# sd2iec_sd_long.net
KiCad netlist of a schematic drawn in EAGLE
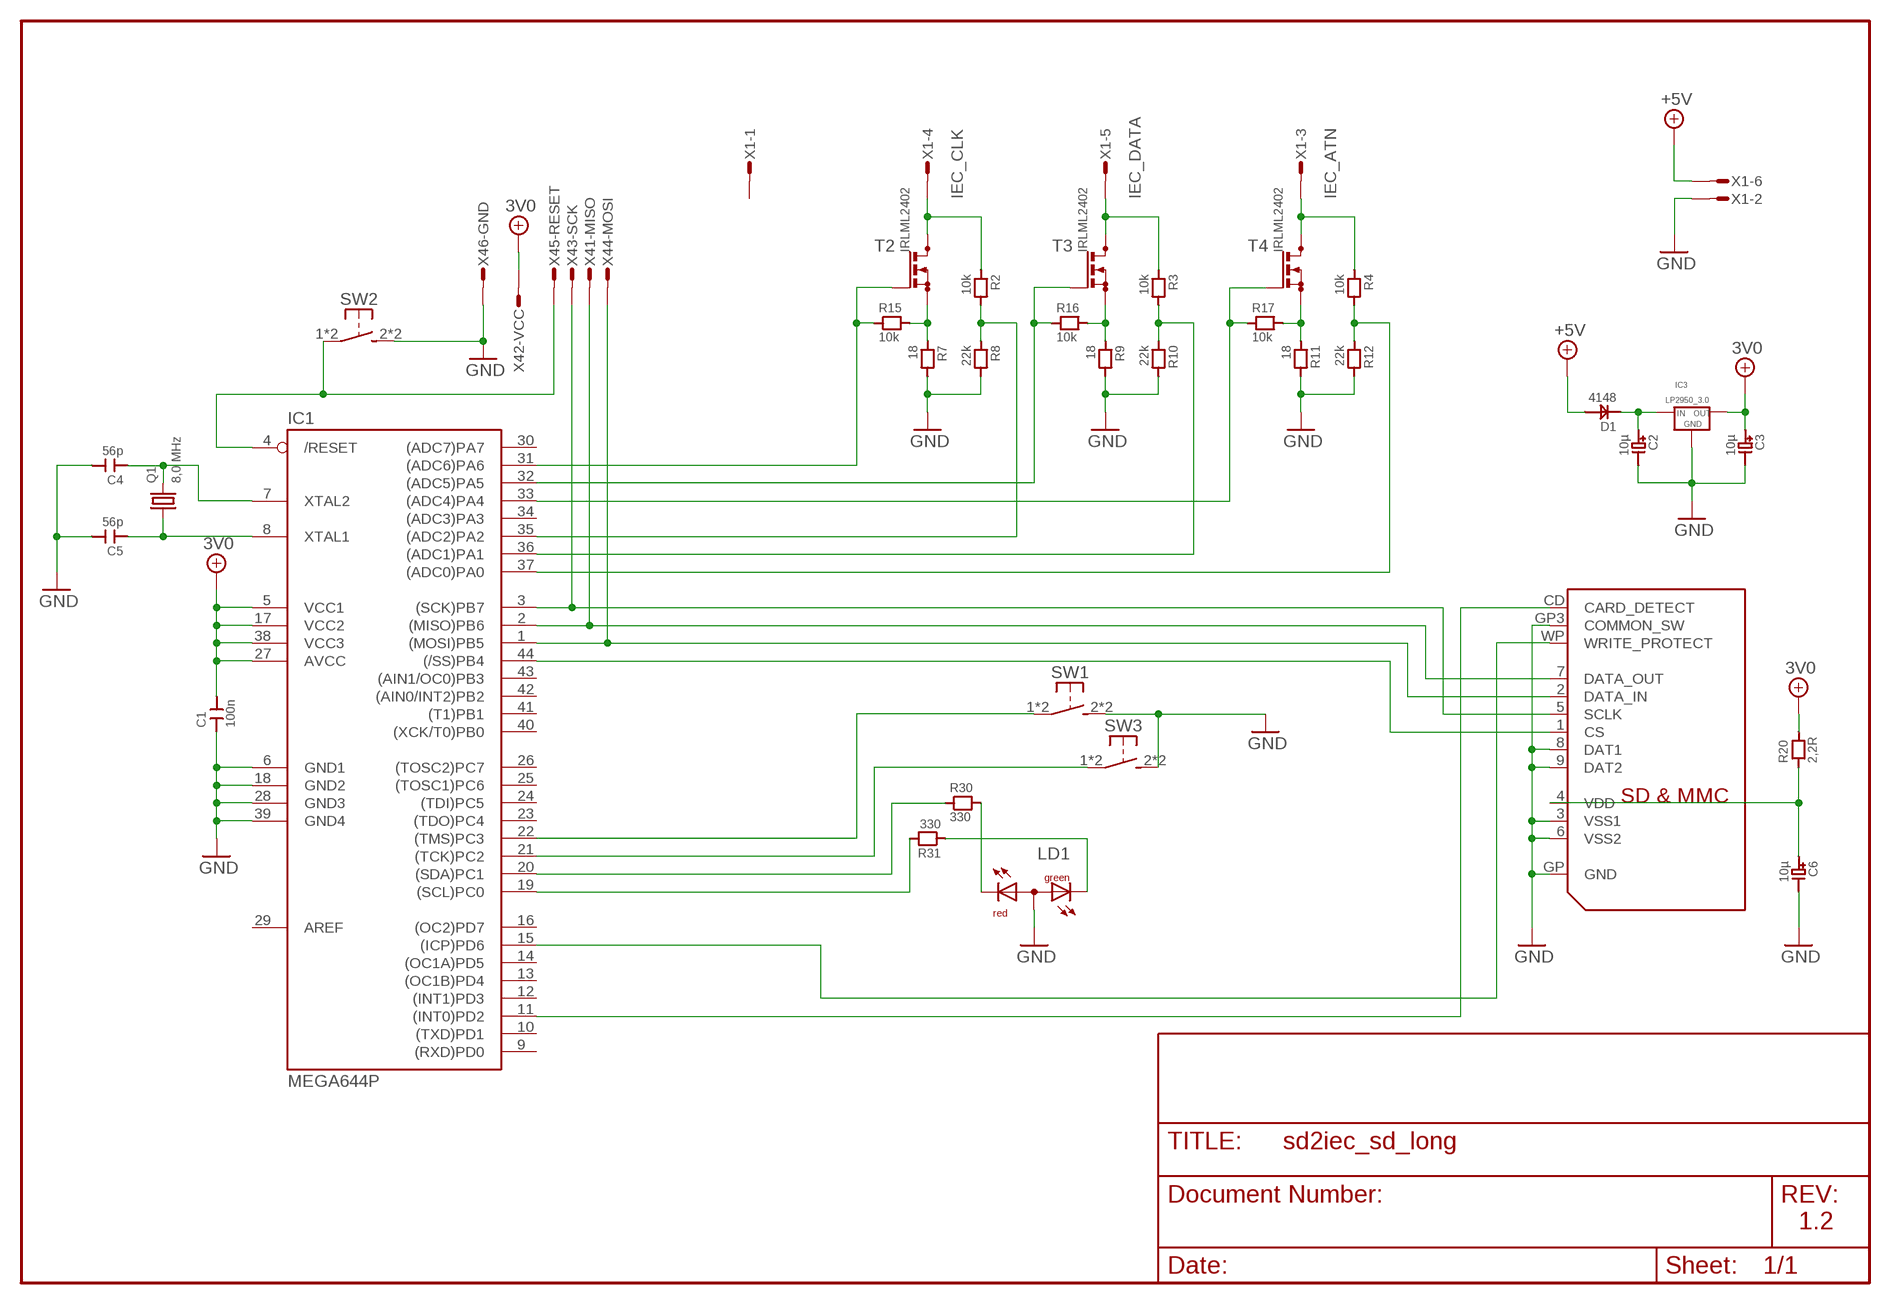
[diagram p0: schematic, sheet 1]

(export (version "E")
  (design (tool "Eeschema 10.0.6"))
  (components
    (comp (ref "C1")
      (value "100n")
      (footprint "eagle-import:C1206")
      (libsource (lib "eagle-import") (part "C1206"))
    )
    (comp (ref "C2")
      (value "10µ")
      (footprint "eagle-import:C_TANTAL_A")
      (libsource (lib "eagle-import") (part "C_POLTA_A"))
    )
    (comp (ref "C3")
      (value "10µ")
      (footprint "eagle-import:C_TANTAL_A")
      (libsource (lib "eagle-import") (part "C_POLTA_A"))
    )
    (comp (ref "C4")
      (value "56p")
      (footprint "eagle-import:C1206")
      (libsource (lib "eagle-import") (part "C1206"))
    )
    (comp (ref "C5")
      (value "56p")
      (footprint "eagle-import:C1206")
      (libsource (lib "eagle-import") (part "C1206"))
    )
    (comp (ref "C6")
      (value "10µ")
      (footprint "eagle-import:C_TANTAL_A")
      (libsource (lib "eagle-import") (part "C_POLTA_A"))
    )
    (comp (ref "D1")
      (value "4148")
      (footprint "eagle-import:SOD-123")
      (libsource (lib "eagle-import") (part "DSOD-123"))
    )
    (comp (ref "IC1")
      (value "MEGA644P")
      (footprint "eagle-import:TQFP44")
      (libsource (lib "eagle-import") (part "MEGA16/32TQFP"))
    )
    (comp (ref "IC3")
      (value "LP2950_3.0")
      (footprint "eagle-import:TO92_S")
      (libsource (lib "eagle-import") (part "LP2950_TO92S"))
    )
    (comp (ref "LD1")
      (value "DUOLED-RG-A")
      (footprint "eagle-import:DUOLED-A-5MM")
      (libsource (lib "eagle-import") (part "DUOLED-RG-A"))
    )
    (comp (ref "Q1")
      (value "8,0 MHz")
      (footprint "eagle-import:HC49_S")
      (libsource (lib "eagle-import") (part "HC49"))
    )
    (comp (ref "R2")
      (value "10k")
      (footprint "eagle-import:R1206")
      (libsource (lib "eagle-import") (part "R1206"))
    )
    (comp (ref "R3")
      (value "10k")
      (footprint "eagle-import:R1206")
      (libsource (lib "eagle-import") (part "R1206"))
    )
    (comp (ref "R4")
      (value "10k")
      (footprint "eagle-import:R1206")
      (libsource (lib "eagle-import") (part "R1206"))
    )
    (comp (ref "R7")
      (value "18")
      (footprint "eagle-import:R1206")
      (libsource (lib "eagle-import") (part "R1206"))
    )
    (comp (ref "R8")
      (value "22k")
      (footprint "eagle-import:R1206")
      (libsource (lib "eagle-import") (part "R1206"))
    )
    (comp (ref "R9")
      (value "18")
      (footprint "eagle-import:R1206")
      (libsource (lib "eagle-import") (part "R1206"))
    )
    (comp (ref "R10")
      (value "22k")
      (footprint "eagle-import:R1206")
      (libsource (lib "eagle-import") (part "R1206"))
    )
    (comp (ref "R11")
      (value "18")
      (footprint "eagle-import:R1206")
      (libsource (lib "eagle-import") (part "R1206"))
    )
    (comp (ref "R12")
      (value "22k")
      (footprint "eagle-import:R1206")
      (libsource (lib "eagle-import") (part "R1206"))
    )
    (comp (ref "R15")
      (value "10k")
      (footprint "eagle-import:R0805")
      (libsource (lib "eagle-import") (part "R0805"))
    )
    (comp (ref "R16")
      (value "10k")
      (footprint "eagle-import:R0805")
      (libsource (lib "eagle-import") (part "R0805"))
    )
    (comp (ref "R17")
      (value "10k")
      (footprint "eagle-import:R0805")
      (libsource (lib "eagle-import") (part "R0805"))
    )
    (comp (ref "R20")
      (value "2,2R")
      (footprint "eagle-import:R1206")
      (libsource (lib "eagle-import") (part "R1206"))
    )
    (comp (ref "R30")
      (value "330")
      (footprint "eagle-import:R1206")
      (libsource (lib "eagle-import") (part "R1206"))
    )
    (comp (ref "R31")
      (value "330")
      (footprint "eagle-import:R1206")
      (libsource (lib "eagle-import") (part "R1206"))
    )
    (comp (ref "SW1")
      (value "Disk Next")
      (footprint "eagle-import:TL3305")
      (libsource (lib "eagle-import") (part "SW-TACTILE-TL3305"))
    )
    (comp (ref "SW2")
      (value "Reset")
      (footprint "eagle-import:TL3305")
      (libsource (lib "eagle-import") (part "SW-TACTILE-TL3305"))
    )
    (comp (ref "SW3")
      (value "Disk Prev")
      (footprint "eagle-import:TL3305")
      (libsource (lib "eagle-import") (part "SW-TACTILE-TL3305"))
    )
    (comp (ref "T2")
      (value "IRLML2402")
      (footprint "eagle-import:SOT23_C")
      (libsource (lib "eagle-import") (part "BSN20_C"))
    )
    (comp (ref "T3")
      (value "IRLML2402")
      (footprint "eagle-import:SOT23_C")
      (libsource (lib "eagle-import") (part "BSN20_C"))
    )
    (comp (ref "T4")
      (value "IRLML2402")
      (footprint "eagle-import:SOT23_C")
      (libsource (lib "eagle-import") (part "BSN20_C"))
    )
    (comp (ref "U$6")
      (value "SDMMC06132")
      (footprint "eagle-import:06132")
      (libsource (lib "eagle-import") (part "SDMMC06132"))
    )
    (comp (ref "X1")
      (value "MICROMATCH-6_PIN")
      (footprint "eagle-import:MICROMATCH-6")
      (libsource (lib "eagle-import") (part "MICROMATCH-6_PIN"))
    )
    (comp (ref "X4")
      (value "AVR-ISP_1X6")
      (footprint "eagle-import:1X6_ISP")
      (libsource (lib "eagle-import") (part "AVR-ISP_1X6"))
    )
  )
  (nets
    (net (code "1") (name "+5V") (class "Default")
      (node (ref "D1") (pin "2") (pinfunction "2_2") (pintype "passive"))
      (node (ref "X1") (pin "6") (pinfunction "S_6") (pintype "passive"))
    )
    (net (code "2") (name "/IEC_ATN") (class "Default")
      (node (ref "R4") (pin "1") (pinfunction "1_1") (pintype "passive"))
      (node (ref "T4") (pin "3") (pinfunction "D_3") (pintype "passive"))
      (node (ref "X1") (pin "3") (pinfunction "S_3") (pintype "passive"))
    )
    (net (code "3") (name "/IEC_CLK") (class "Default")
      (node (ref "R2") (pin "1") (pinfunction "1_1") (pintype "passive"))
      (node (ref "T2") (pin "3") (pinfunction "D_3") (pintype "passive"))
      (node (ref "X1") (pin "4") (pinfunction "S_4") (pintype "passive"))
    )
    (net (code "4") (name "/IEC_DATA") (class "Default")
      (node (ref "R3") (pin "1") (pinfunction "1_1") (pintype "passive"))
      (node (ref "T3") (pin "3") (pinfunction "D_3") (pintype "passive"))
      (node (ref "X1") (pin "5") (pinfunction "S_5") (pintype "passive"))
    )
    (net (code "5") (name "3V0") (class "Default")
      (node (ref "C1") (pin "2") (pinfunction "2_2") (pintype "passive"))
      (node (ref "C3") (pin "1") (pinfunction "1_1") (pintype "passive"))
      (node (ref "IC1") (pin "17") (pinfunction "VCC2_17") (pintype "power_in"))
      (node (ref "IC1") (pin "27") (pinfunction "AVCC_27") (pintype "power_in"))
      (node (ref "IC1") (pin "38") (pinfunction "VCC3_38") (pintype "power_in"))
      (node (ref "IC1") (pin "5") (pinfunction "VCC1_5") (pintype "power_in"))
      (node (ref "IC3") (pin "3") (pinfunction "OUT_3") (pintype "passive"))
      (node (ref "R20") (pin "2") (pinfunction "2_2") (pintype "passive"))
      (node (ref "X4") (pin "2") (pinfunction "S_2") (pintype "passive"))
    )
    (net (code "6") (name "GND") (class "Default")
      (node (ref "C1") (pin "1") (pinfunction "1_1") (pintype "passive"))
      (node (ref "C2") (pin "2") (pinfunction "2_2") (pintype "passive"))
      (node (ref "C3") (pin "2") (pinfunction "2_2") (pintype "passive"))
      (node (ref "C4") (pin "2") (pinfunction "2_2") (pintype "passive"))
      (node (ref "C5") (pin "2") (pinfunction "2_2") (pintype "passive"))
      (node (ref "C6") (pin "2") (pinfunction "2_2") (pintype "passive"))
      (node (ref "IC1") (pin "18") (pinfunction "GND2_18") (pintype "power_in"))
      (node (ref "IC1") (pin "28") (pinfunction "GND3_28") (pintype "power_in"))
      (node (ref "IC1") (pin "39") (pinfunction "GND4_39") (pintype "power_in"))
      (node (ref "IC1") (pin "6") (pinfunction "GND1_6") (pintype "power_in"))
      (node (ref "IC3") (pin "2") (pinfunction "GND_2") (pintype "input"))
      (node (ref "LD1") (pin "A") (pinfunction "A_A") (pintype "passive"))
      (node (ref "R10") (pin "2") (pinfunction "2_2") (pintype "passive"))
      (node (ref "R11") (pin "2") (pinfunction "2_2") (pintype "passive"))
      (node (ref "R12") (pin "2") (pinfunction "2_2") (pintype "passive"))
      (node (ref "R7") (pin "2") (pinfunction "2_2") (pintype "passive"))
      (node (ref "R8") (pin "2") (pinfunction "2_2") (pintype "passive"))
      (node (ref "R9") (pin "2") (pinfunction "2_2") (pintype "passive"))
      (node (ref "SW1") (pin "2") (pinfunction "S1_2") (pintype "passive"))
      (node (ref "SW1") (pin "3") (pinfunction "S1_3") (pintype "passive"))
      (node (ref "SW2") (pin "2") (pinfunction "S1_2") (pintype "passive"))
      (node (ref "SW2") (pin "3") (pinfunction "S1_3") (pintype "passive"))
      (node (ref "SW3") (pin "2") (pinfunction "S1_2") (pintype "passive"))
      (node (ref "SW3") (pin "3") (pinfunction "S1_3") (pintype "passive"))
      (node (ref "U$6") (pin "3") (pinfunction "VSS1_3") (pintype "power_in"))
      (node (ref "U$6") (pin "6") (pinfunction "VSS2_6") (pintype "power_in"))
      (node (ref "U$6") (pin "8") (pinfunction "DAT1_8") (pintype "bidirectional"))
      (node (ref "U$6") (pin "9") (pinfunction "DAT2_9") (pintype "bidirectional"))
      (node (ref "U$6") (pin "GP") (pinfunction "GND_GP") (pintype "power_in"))
      (node (ref "U$6") (pin "GP3") (pinfunction "COMMON_SW_GP3") (pintype "passive"))
      (node (ref "X1") (pin "2") (pinfunction "S_2") (pintype "passive"))
      (node (ref "X4") (pin "6") (pinfunction "S_6") (pintype "passive"))
    )
    (net (code "7") (name "Net-(IC1-(ADC0)PA0)") (class "Default")
      (node (ref "IC1") (pin "37") (pinfunction "(ADC0)PA0_37") (pintype "bidirectional"))
      (node (ref "R12") (pin "1") (pinfunction "1_1") (pintype "passive"))
      (node (ref "R4") (pin "2") (pinfunction "2_2") (pintype "passive"))
    )
    (net (code "8") (name "Net-(IC1-(ADC1)PA1)") (class "Default")
      (node (ref "IC1") (pin "36") (pinfunction "(ADC1)PA1_36") (pintype "bidirectional"))
      (node (ref "R10") (pin "1") (pinfunction "1_1") (pintype "passive"))
      (node (ref "R3") (pin "2") (pinfunction "2_2") (pintype "passive"))
    )
    (net (code "9") (name "Net-(IC1-(ADC2)PA2)") (class "Default")
      (node (ref "IC1") (pin "35") (pinfunction "(ADC2)PA2_35") (pintype "bidirectional"))
      (node (ref "R2") (pin "2") (pinfunction "2_2") (pintype "passive"))
      (node (ref "R8") (pin "1") (pinfunction "1_1") (pintype "passive"))
    )
    (net (code "10") (name "Net-(IC1-(ADC4)PA4)") (class "Default")
      (node (ref "IC1") (pin "33") (pinfunction "(ADC4)PA4_33") (pintype "bidirectional"))
      (node (ref "R17") (pin "1") (pinfunction "1_1") (pintype "passive"))
      (node (ref "T4") (pin "1") (pinfunction "G_1") (pintype "passive"))
    )
    (net (code "11") (name "Net-(IC1-(ADC5)PA5)") (class "Default")
      (node (ref "IC1") (pin "32") (pinfunction "(ADC5)PA5_32") (pintype "bidirectional"))
      (node (ref "R16") (pin "1") (pinfunction "1_1") (pintype "passive"))
      (node (ref "T3") (pin "1") (pinfunction "G_1") (pintype "passive"))
    )
    (net (code "12") (name "Net-(IC1-(ADC6)PA6)") (class "Default")
      (node (ref "IC1") (pin "31") (pinfunction "(ADC6)PA6_31") (pintype "bidirectional"))
      (node (ref "R15") (pin "1") (pinfunction "1_1") (pintype "passive"))
      (node (ref "T2") (pin "1") (pinfunction "G_1") (pintype "passive"))
    )
    (net (code "13") (name "Net-(IC1-(ICP)PD6)") (class "Default")
      (node (ref "IC1") (pin "15") (pinfunction "(ICP)PD6_15") (pintype "bidirectional"))
      (node (ref "U$6") (pin "WP") (pinfunction "WRITE_PROTECT_WP") (pintype "passive"))
    )
    (net (code "14") (name "Net-(IC1-(INT0)PD2)") (class "Default")
      (node (ref "IC1") (pin "11") (pinfunction "(INT0)PD2_11") (pintype "bidirectional"))
      (node (ref "U$6") (pin "CD") (pinfunction "CARD_DETECT_CD") (pintype "passive"))
    )
    (net (code "15") (name "Net-(IC1-(MISO)PB6)") (class "Default")
      (node (ref "IC1") (pin "2") (pinfunction "(MISO)PB6_2") (pintype "bidirectional"))
      (node (ref "U$6") (pin "7") (pinfunction "DATA_OUT_7") (pintype "output"))
      (node (ref "X4") (pin "1") (pinfunction "S_1") (pintype "passive"))
    )
    (net (code "16") (name "Net-(IC1-(MOSI)PB5)") (class "Default")
      (node (ref "IC1") (pin "1") (pinfunction "(MOSI)PB5_1") (pintype "bidirectional"))
      (node (ref "U$6") (pin "2") (pinfunction "DATA_IN_2") (pintype "input"))
      (node (ref "X4") (pin "4") (pinfunction "S_4") (pintype "passive"))
    )
    (net (code "17") (name "Net-(IC1-(SCK)PB7)") (class "Default")
      (node (ref "IC1") (pin "3") (pinfunction "(SCK)PB7_3") (pintype "bidirectional"))
      (node (ref "U$6") (pin "5") (pinfunction "SCLK_5") (pintype "input"))
      (node (ref "X4") (pin "3") (pinfunction "S_3") (pintype "passive"))
    )
    (net (code "18") (name "Net-(IC1-(SCL)PC0)") (class "Default")
      (node (ref "IC1") (pin "19") (pinfunction "(SCL)PC0_19") (pintype "bidirectional"))
      (node (ref "R31") (pin "2") (pinfunction "2_2") (pintype "passive"))
    )
    (net (code "19") (name "Net-(IC1-(SDA)PC1)") (class "Default")
      (node (ref "IC1") (pin "20") (pinfunction "(SDA)PC1_20") (pintype "bidirectional"))
      (node (ref "R30") (pin "1") (pinfunction "1_1") (pintype "passive"))
    )
    (net (code "20") (name "Net-(IC1-(TCK)PC2)") (class "Default")
      (node (ref "IC1") (pin "21") (pinfunction "(TCK)PC2_21") (pintype "bidirectional"))
      (node (ref "SW3") (pin "1") (pinfunction "P1_1") (pintype "passive"))
      (node (ref "SW3") (pin "4") (pinfunction "P1_4") (pintype "passive"))
    )
    (net (code "21") (name "Net-(IC1-(TMS)PC3)") (class "Default")
      (node (ref "IC1") (pin "22") (pinfunction "(TMS)PC3_22") (pintype "bidirectional"))
      (node (ref "SW1") (pin "1") (pinfunction "P1_1") (pintype "passive"))
      (node (ref "SW1") (pin "4") (pinfunction "P1_4") (pintype "passive"))
    )
    (net (code "22") (name "Net-(IC1-({slash}SS)PB4)") (class "Default")
      (node (ref "IC1") (pin "44") (pinfunction "(/SS)PB4_44") (pintype "bidirectional"))
      (node (ref "U$6") (pin "1") (pinfunction "CS_1") (pintype "input"))
    )
    (net (code "23") (name "Net-(IC1-XTAL1)") (class "Default")
      (node (ref "C5") (pin "1") (pinfunction "1_1") (pintype "passive"))
      (node (ref "IC1") (pin "8") (pinfunction "XTAL1_8") (pintype "input"))
      (node (ref "Q1") (pin "1") (pinfunction "1_1") (pintype "passive"))
    )
    (net (code "24") (name "Net-(IC1-XTAL2)") (class "Default")
      (node (ref "C4") (pin "1") (pinfunction "1_1") (pintype "passive"))
      (node (ref "IC1") (pin "7") (pinfunction "XTAL2_7") (pintype "input"))
      (node (ref "Q1") (pin "2") (pinfunction "2_2") (pintype "passive"))
    )
    (net (code "25") (name "Net-(IC1-{slash}RESET)") (class "Default")
      (node (ref "IC1") (pin "4") (pinfunction "/RESET_4") (pintype "input"))
      (node (ref "SW2") (pin "1") (pinfunction "P1_1") (pintype "passive"))
      (node (ref "SW2") (pin "4") (pinfunction "P1_4") (pintype "passive"))
      (node (ref "X4") (pin "5") (pinfunction "S_5") (pintype "passive"))
    )
    (net (code "26") (name "Net-(IC3-IN)") (class "Default")
      (node (ref "C2") (pin "1") (pinfunction "1_1") (pintype "passive"))
      (node (ref "D1") (pin "1") (pinfunction "1_1") (pintype "passive"))
      (node (ref "IC3") (pin "1") (pinfunction "IN_1") (pintype "input"))
    )
    (net (code "27") (name "Net-(LD1-CG)") (class "Default")
      (node (ref "LD1") (pin "CX") (pinfunction "CG_CX") (pintype "passive"))
      (node (ref "R31") (pin "1") (pinfunction "1_1") (pintype "passive"))
    )
    (net (code "28") (name "Net-(LD1-PadCR)") (class "Default")
      (node (ref "LD1") (pin "CR") (pinfunction "CR_CR") (pintype "passive"))
      (node (ref "R30") (pin "2") (pinfunction "2_2") (pintype "passive"))
    )
    (net (code "29") (name "Net-(T2-S)") (class "Default")
      (node (ref "R15") (pin "2") (pinfunction "2_2") (pintype "passive"))
      (node (ref "R7") (pin "1") (pinfunction "1_1") (pintype "passive"))
      (node (ref "T2") (pin "2") (pinfunction "S_2") (pintype "passive"))
    )
    (net (code "30") (name "Net-(T3-S)") (class "Default")
      (node (ref "R16") (pin "2") (pinfunction "2_2") (pintype "passive"))
      (node (ref "R9") (pin "1") (pinfunction "1_1") (pintype "passive"))
      (node (ref "T3") (pin "2") (pinfunction "S_2") (pintype "passive"))
    )
    (net (code "31") (name "Net-(T4-S)") (class "Default")
      (node (ref "R11") (pin "1") (pinfunction "1_1") (pintype "passive"))
      (node (ref "R17") (pin "2") (pinfunction "2_2") (pintype "passive"))
      (node (ref "T4") (pin "2") (pinfunction "S_2") (pintype "passive"))
    )
    (net (code "32") (name "Net-(U$6-VDD)") (class "Default")
      (node (ref "C6") (pin "1") (pinfunction "1_1") (pintype "passive"))
      (node (ref "R20") (pin "1") (pinfunction "1_1") (pintype "passive"))
      (node (ref "U$6") (pin "4") (pinfunction "VDD_4") (pintype "power_in"))
    )
    (net (code "33") (name "unconnected-(IC1-(ADC3)PA3-Pad34)") (class "Default")
      (node (ref "IC1") (pin "34") (pinfunction "(ADC3)PA3_34") (pintype "bidirectional"))
    )
    (net (code "34") (name "unconnected-(IC1-(ADC7)PA7-Pad30)") (class "Default")
      (node (ref "IC1") (pin "30") (pinfunction "(ADC7)PA7_30") (pintype "bidirectional"))
    )
    (net (code "35") (name "unconnected-(IC1-(AIN0{slash}INT2)PB2-Pad42)") (class "Default")
      (node (ref "IC1") (pin "42") (pinfunction "(AIN0/INT2)PB2_42") (pintype "bidirectional"))
    )
    (net (code "36") (name "unconnected-(IC1-(AIN1{slash}OC0)PB3-Pad43)") (class "Default")
      (node (ref "IC1") (pin "43") (pinfunction "(AIN1/OC0)PB3_43") (pintype "bidirectional"))
    )
    (net (code "37") (name "unconnected-(IC1-(INT1)PD3-Pad12)") (class "Default")
      (node (ref "IC1") (pin "12") (pinfunction "(INT1)PD3_12") (pintype "bidirectional"))
    )
    (net (code "38") (name "unconnected-(IC1-(OC1A)PD5-Pad14)") (class "Default")
      (node (ref "IC1") (pin "14") (pinfunction "(OC1A)PD5_14") (pintype "bidirectional"))
    )
    (net (code "39") (name "unconnected-(IC1-(OC1B)PD4-Pad13)") (class "Default")
      (node (ref "IC1") (pin "13") (pinfunction "(OC1B)PD4_13") (pintype "bidirectional"))
    )
    (net (code "40") (name "unconnected-(IC1-(OC2)PD7-Pad16)") (class "Default")
      (node (ref "IC1") (pin "16") (pinfunction "(OC2)PD7_16") (pintype "bidirectional"))
    )
    (net (code "41") (name "unconnected-(IC1-(RXD)PD0-Pad9)") (class "Default")
      (node (ref "IC1") (pin "9") (pinfunction "(RXD)PD0_9") (pintype "bidirectional"))
    )
    (net (code "42") (name "unconnected-(IC1-(T1)PB1-Pad41)") (class "Default")
      (node (ref "IC1") (pin "41") (pinfunction "(T1)PB1_41") (pintype "bidirectional"))
    )
    (net (code "43") (name "unconnected-(IC1-(TDI)PC5-Pad24)") (class "Default")
      (node (ref "IC1") (pin "24") (pinfunction "(TDI)PC5_24") (pintype "bidirectional"))
    )
    (net (code "44") (name "unconnected-(IC1-(TDO)PC4-Pad23)") (class "Default")
      (node (ref "IC1") (pin "23") (pinfunction "(TDO)PC4_23") (pintype "bidirectional"))
    )
    (net (code "45") (name "unconnected-(IC1-(TOSC1)PC6-Pad25)") (class "Default")
      (node (ref "IC1") (pin "25") (pinfunction "(TOSC1)PC6_25") (pintype "bidirectional"))
    )
    (net (code "46") (name "unconnected-(IC1-(TOSC2)PC7-Pad26)") (class "Default")
      (node (ref "IC1") (pin "26") (pinfunction "(TOSC2)PC7_26") (pintype "bidirectional"))
    )
    (net (code "47") (name "unconnected-(IC1-(TXD)PD1-Pad10)") (class "Default")
      (node (ref "IC1") (pin "10") (pinfunction "(TXD)PD1_10") (pintype "bidirectional"))
    )
    (net (code "48") (name "unconnected-(IC1-(XCK{slash}T0)PB0-Pad40)") (class "Default")
      (node (ref "IC1") (pin "40") (pinfunction "(XCK/T0)PB0_40") (pintype "bidirectional"))
    )
    (net (code "49") (name "unconnected-(IC1-AREF-Pad29)") (class "Default")
      (node (ref "IC1") (pin "29") (pinfunction "AREF_29") (pintype "bidirectional"))
    )
    (net (code "50") (name "unconnected-(X1A-S-Pad1)") (class "Default")
      (node (ref "X1") (pin "1") (pinfunction "S_1") (pintype "passive"))
    )
  )
)
